# tritiled22_lux_c.net
KiCad netlist of a schematic drawn in EAGLE
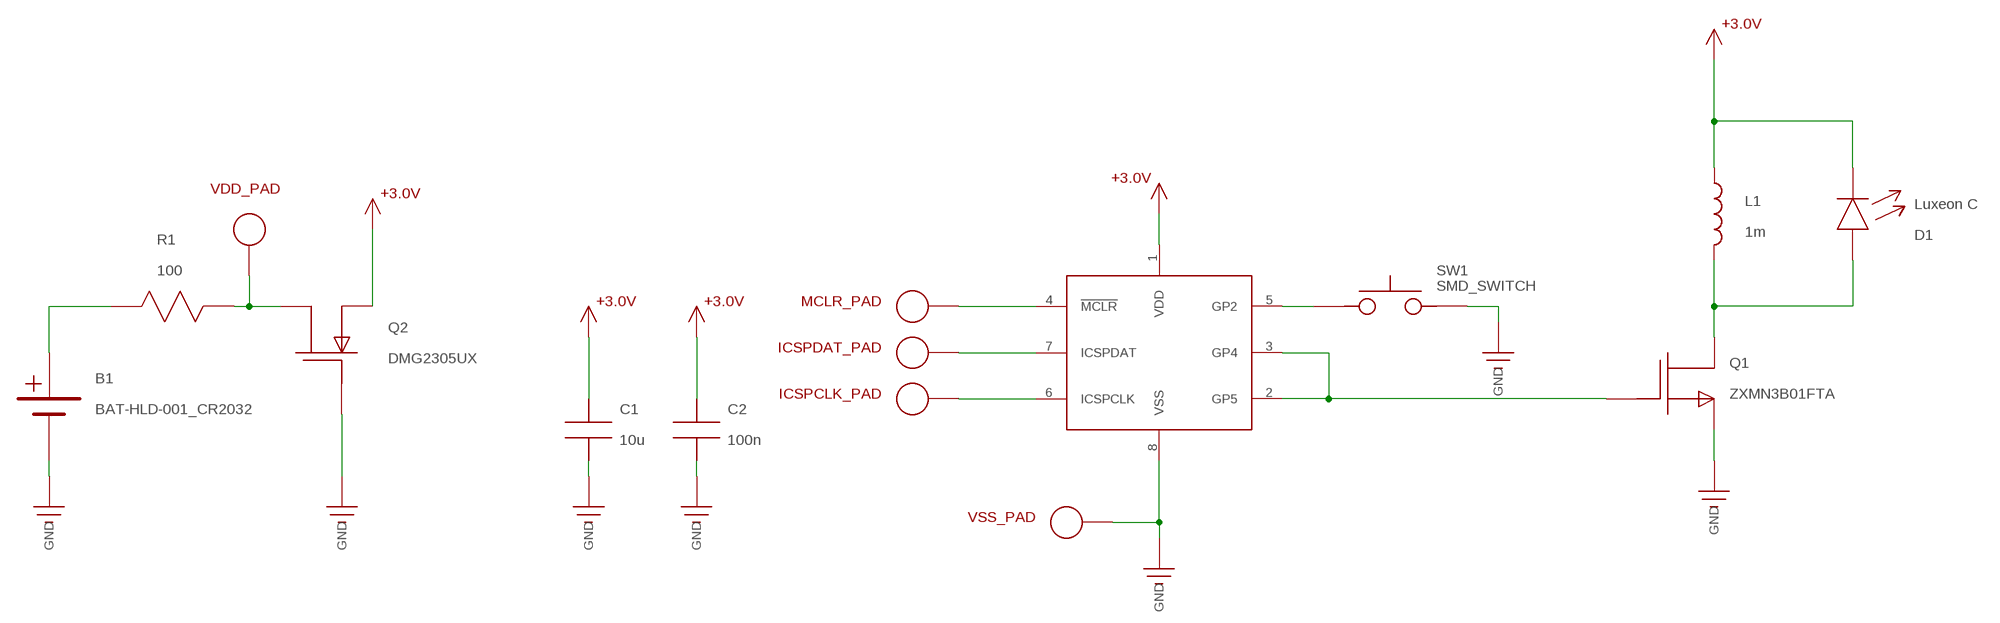
[diagram p0: schematic, sheet 1]

(export (version "E")
  (design (tool "Eeschema 10.0.6"))
  (components
    (comp (ref "B1")
      (value "BAT-HLD-001_CR2032")
      (footprint "eagle-import:CR2032_BAT-HLD_001")
      (libsource (lib "eagle-import") (part "BAT-HLD-001_CR2032"))
    )
    (comp (ref "C1")
      (value "10u")
      (footprint "eagle-import:1206")
      (libsource (lib "eagle-import") (part "C1206"))
    )
    (comp (ref "C2")
      (value "100n")
      (footprint "eagle-import:0805")
      (libsource (lib "eagle-import") (part "C0805"))
    )
    (comp (ref "D1")
      (value "Luxeon C")
      (footprint "eagle-import:LUXEON_C")
      (libsource (lib "eagle-import") (part "LEDLUXEON_C"))
    )
    (comp (ref "ICSPCLK_PAD")
      (value "ICSP_PAD")
      (footprint "eagle-import:ICSP_PAD")
      (libsource (lib "eagle-import") (part "ICSP_PAD"))
    )
    (comp (ref "ICSPDAT_PAD")
      (value "ICSP_PAD")
      (footprint "eagle-import:ICSP_PAD")
      (libsource (lib "eagle-import") (part "ICSP_PAD"))
    )
    (comp (ref "L1")
      (value "1m")
      (footprint "eagle-import:SRR6028_INDUCTOR")
      (libsource (lib "eagle-import") (part "SRR6028_INDUCTOR"))
    )
    (comp (ref "MCLR_PAD")
      (value "ICSP_PAD")
      (footprint "eagle-import:ICSP_PAD")
      (libsource (lib "eagle-import") (part "ICSP_PAD"))
    )
    (comp (ref "Q1")
      (value "ZXMN3B01FTA")
      (footprint "eagle-import:SOT-23")
      (libsource (lib "eagle-import") (part "ZXMN3B01FSOT23"))
    )
    (comp (ref "Q2")
      (value "DMG2305UX")
      (footprint "eagle-import:SOT-23")
      (libsource (lib "eagle-import") (part "DMG2305UXSOT23"))
    )
    (comp (ref "R1")
      (value "100")
      (footprint "eagle-import:R1206")
      (libsource (lib "eagle-import") (part "R1206"))
    )
    (comp (ref "SW1")
      (value "SMD_SWITCH")
      (footprint "eagle-import:SMD_SWITCH")
      (libsource (lib "eagle-import") (part "SMD_SWITCH"))
    )
    (comp (ref "U1")
      (value "PIC12LF1571")
      (footprint "eagle-import:SOIC8")
      (libsource (lib "eagle-import") (part "PIC12LF1571"))
    )
    (comp (ref "VDD_PAD")
      (value "ICSP_PAD")
      (footprint "eagle-import:ICSP_PAD")
      (libsource (lib "eagle-import") (part "ICSP_PAD"))
    )
    (comp (ref "VSS_PAD")
      (value "ICSP_PAD")
      (footprint "eagle-import:ICSP_PAD")
      (libsource (lib "eagle-import") (part "ICSP_PAD"))
    )
  )
  (nets
    (net (code "1") (name "+3.0V") (class "Default")
      (node (ref "C1") (pin "P$1") (pinfunction "P$1_P$1") (pintype "bidirectional"))
      (node (ref "C2") (pin "P$1") (pinfunction "P$1_P$1") (pintype "bidirectional"))
      (node (ref "D1") (pin "C") (pinfunction "C_C") (pintype "bidirectional"))
      (node (ref "L1") (pin "P$1") (pinfunction "1_P$1") (pintype "passive"))
      (node (ref "Q2") (pin "2") (pinfunction "S_2") (pintype "bidirectional"))
      (node (ref "U1") (pin "1") (pinfunction "VDD_1") (pintype "bidirectional"))
    )
    (net (code "2") (name "GND") (class "Default")
      (node (ref "B1") (pin "GND") (pinfunction "0V_GND") (pintype "power_in"))
      (node (ref "C1") (pin "P$2") (pinfunction "P$2_P$2") (pintype "bidirectional"))
      (node (ref "C2") (pin "P$2") (pinfunction "P$2_P$2") (pintype "bidirectional"))
      (node (ref "Q1") (pin "2") (pinfunction "S_2") (pintype "bidirectional"))
      (node (ref "Q2") (pin "1") (pinfunction "G_1") (pintype "bidirectional"))
      (node (ref "SW1") (pin "P$3") (pinfunction "P$2_P$3") (pintype "bidirectional"))
      (node (ref "SW1") (pin "P$4") (pinfunction "P$2_P$4") (pintype "bidirectional"))
      (node (ref "U1") (pin "8") (pinfunction "VSS_8") (pintype "bidirectional"))
      (node (ref "VSS_PAD") (pin "P$2") (pinfunction "P$1_P$2") (pintype "bidirectional"))
    )
    (net (code "3") (name "Net-(B1-+V-Pad+V1)") (class "Default")
      (node (ref "B1") (pin "+V1") (pinfunction "+V_+V1") (pintype "power_in"))
      (node (ref "B1") (pin "+V2") (pinfunction "+V_+V2") (pintype "power_in"))
      (node (ref "R1") (pin "P$1") (pinfunction "P$1_P$1") (pintype "bidirectional"))
    )
    (net (code "4") (name "Net-(ICSPCLK_PAD-P$1)") (class "Default")
      (node (ref "ICSPCLK_PAD") (pin "P$2") (pinfunction "P$1_P$2") (pintype "bidirectional"))
      (node (ref "U1") (pin "6") (pinfunction "ICSPCLK_6") (pintype "bidirectional"))
    )
    (net (code "5") (name "Net-(ICSPDAT_PAD-P$1)") (class "Default")
      (node (ref "ICSPDAT_PAD") (pin "P$2") (pinfunction "P$1_P$2") (pintype "bidirectional"))
      (node (ref "U1") (pin "7") (pinfunction "ICSPDAT_7") (pintype "bidirectional"))
    )
    (net (code "6") (name "Net-(L1-2)") (class "Default")
      (node (ref "D1") (pin "A") (pinfunction "A_A") (pintype "bidirectional"))
      (node (ref "L1") (pin "P$2") (pinfunction "2_P$2") (pintype "passive"))
      (node (ref "Q1") (pin "3") (pinfunction "D_3") (pintype "bidirectional"))
    )
    (net (code "7") (name "Net-(MCLR_PAD-P$1)") (class "Default")
      (node (ref "MCLR_PAD") (pin "P$2") (pinfunction "P$1_P$2") (pintype "bidirectional"))
      (node (ref "U1") (pin "4") (pinfunction "~{MCLR}_4") (pintype "bidirectional"))
    )
    (net (code "8") (name "Net-(Q1-G)") (class "Default")
      (node (ref "Q1") (pin "1") (pinfunction "G_1") (pintype "bidirectional"))
      (node (ref "U1") (pin "2") (pinfunction "GP5_2") (pintype "bidirectional"))
      (node (ref "U1") (pin "3") (pinfunction "GP4_3") (pintype "bidirectional"))
    )
    (net (code "9") (name "Net-(Q2-D)") (class "Default")
      (node (ref "Q2") (pin "3") (pinfunction "D_3") (pintype "bidirectional"))
      (node (ref "R1") (pin "P$2") (pinfunction "P$2_P$2") (pintype "bidirectional"))
      (node (ref "VDD_PAD") (pin "P$2") (pinfunction "P$1_P$2") (pintype "bidirectional"))
    )
    (net (code "10") (name "Net-(U1-GP2)") (class "Default")
      (node (ref "SW1") (pin "P$1") (pinfunction "P$1_P$1") (pintype "bidirectional"))
      (node (ref "SW1") (pin "P$2") (pinfunction "P$1_P$2") (pintype "bidirectional"))
      (node (ref "U1") (pin "5") (pinfunction "GP2_5") (pintype "bidirectional"))
    )
  )
)
